# mapleCUx_med_011.net
KiCad netlist of a schematic drawn in EAGLE
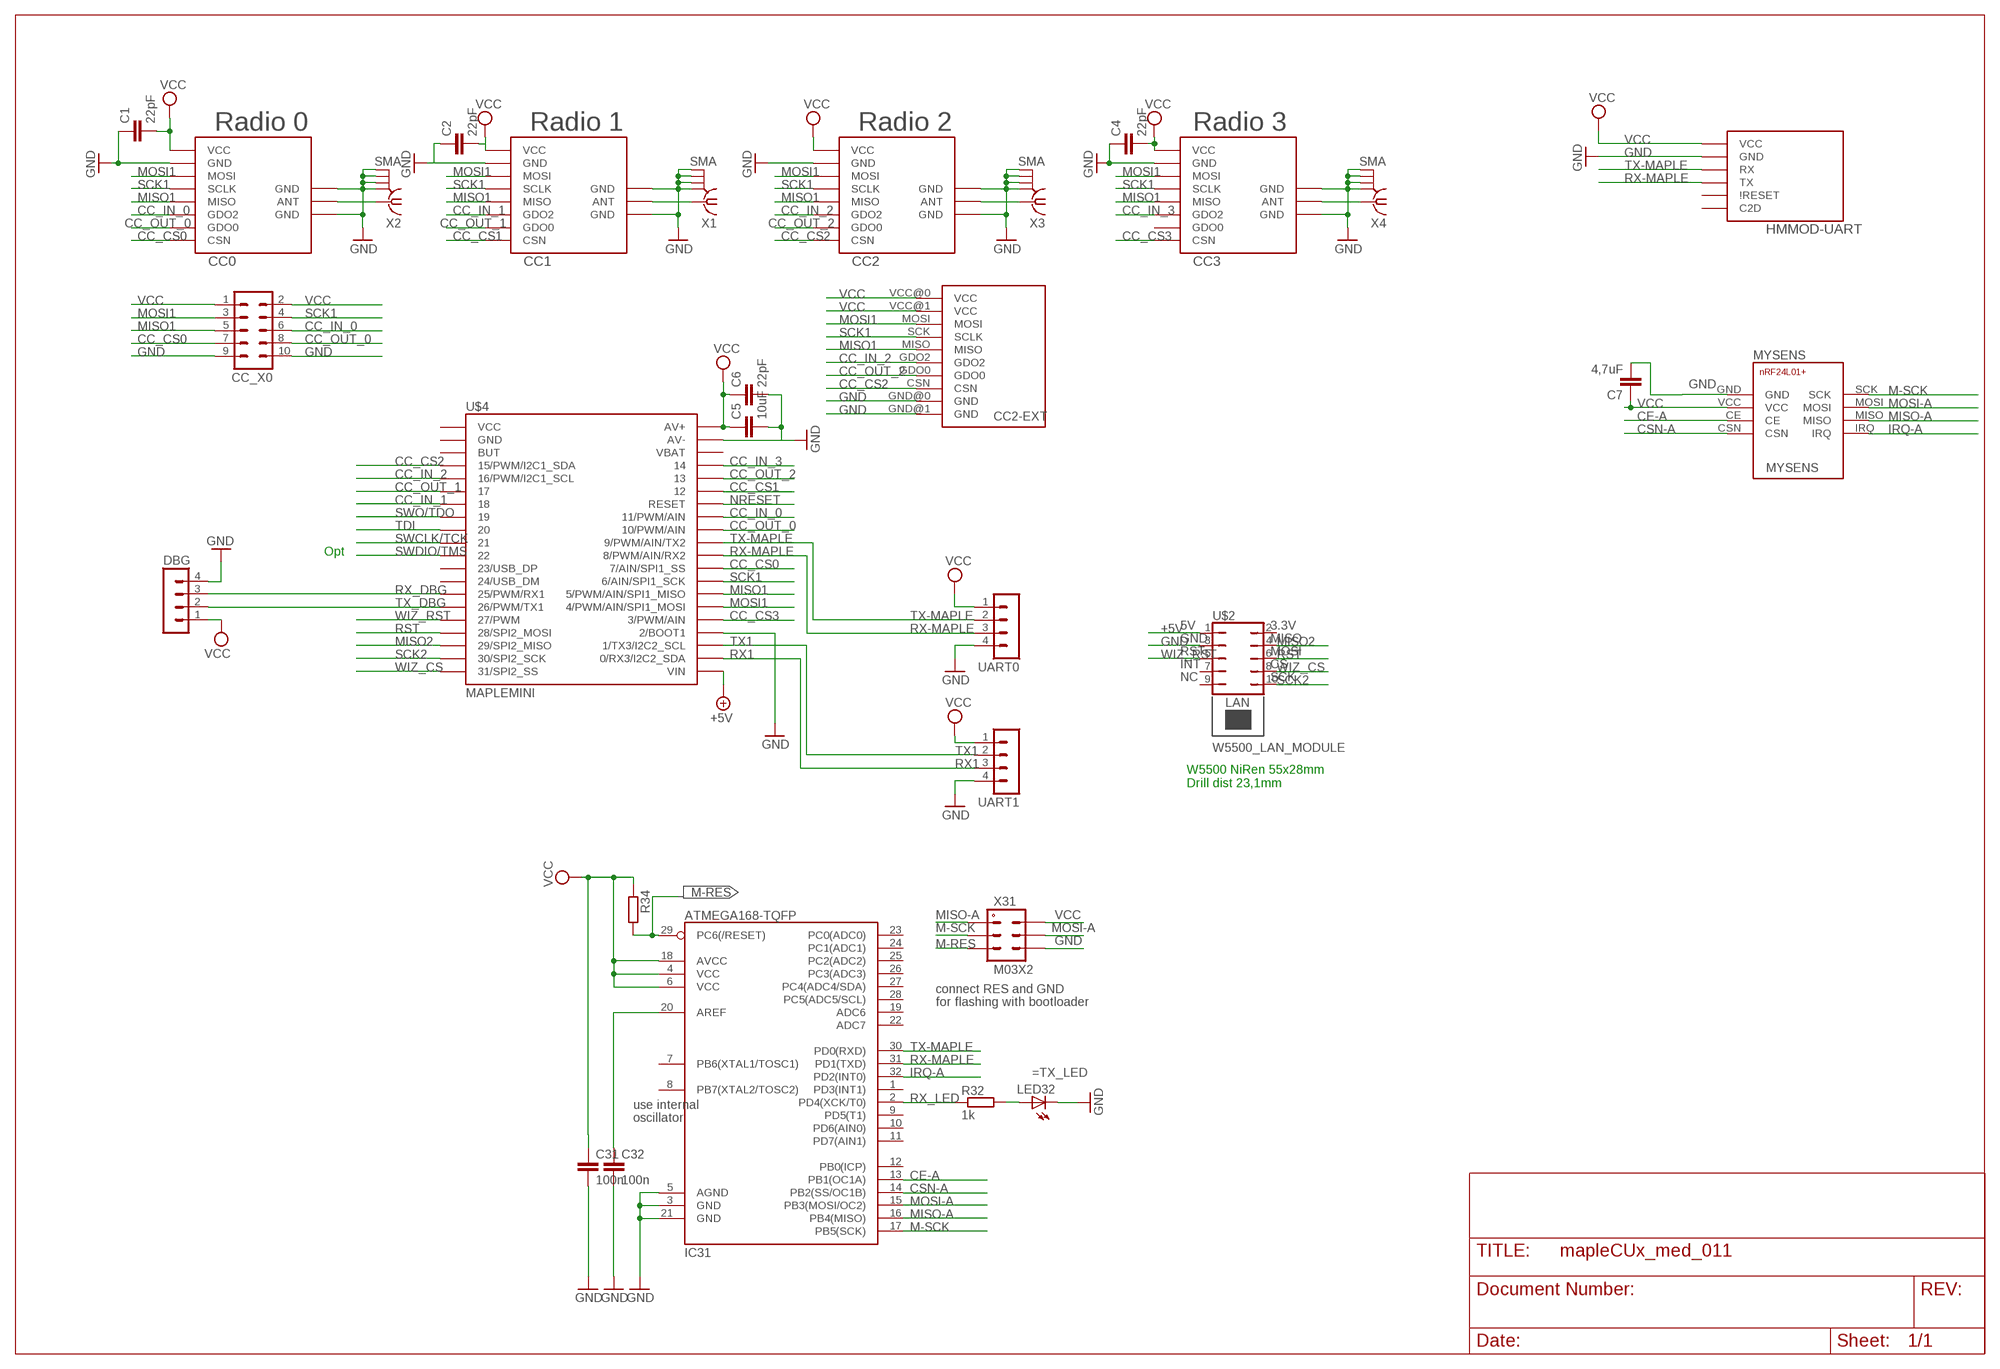
[diagram p0: schematic, sheet 1]

(export (version "E")
  (design (tool "Eeschema 10.0.6"))
  (components
    (comp (ref "C1")
      (value "22pF")
      (footprint "eagle-import:C0805")
      (libsource (lib "eagle-import") (part "C-EUC0805"))
    )
    (comp (ref "C2")
      (value "22pF")
      (footprint "eagle-import:C0805")
      (libsource (lib "eagle-import") (part "C-EUC0805"))
    )
    (comp (ref "C4")
      (value "22pF")
      (footprint "eagle-import:C0805")
      (libsource (lib "eagle-import") (part "C-EUC0805"))
    )
    (comp (ref "C5")
      (value "10uF")
      (footprint "eagle-import:C1210")
      (libsource (lib "eagle-import") (part "C-EUC1210"))
    )
    (comp (ref "C6")
      (value "22pF")
      (footprint "eagle-import:C0805")
      (libsource (lib "eagle-import") (part "C-EUC0805"))
    )
    (comp (ref "C7")
      (value "4,7uF")
      (footprint "eagle-import:C1210")
      (libsource (lib "eagle-import") (part "C-EUC1210"))
    )
    (comp (ref "C31")
      (value "100n")
      (footprint "eagle-import:C0805")
      (libsource (lib "eagle-import") (part "C-EUC0805"))
    )
    (comp (ref "C32")
      (value "100n")
      (footprint "eagle-import:C0805")
      (libsource (lib "eagle-import") (part "C-EUC0805"))
    )
    (comp (ref "CC0")
      (value "CC1101_MODULE1SMD")
      (footprint "eagle-import:CC1101_MODULE1_SMD")
      (libsource (lib "eagle-import") (part "CC1101_MODULE1SMD"))
    )
    (comp (ref "CC1")
      (value "CC1101_MODULE1SMD")
      (footprint "eagle-import:CC1101_MODULE1_SMD")
      (libsource (lib "eagle-import") (part "CC1101_MODULE1SMD"))
    )
    (comp (ref "CC2")
      (value "CC1101_MODULE1SMD")
      (footprint "eagle-import:CC1101_MODULE1_SMD")
      (libsource (lib "eagle-import") (part "CC1101_MODULE1SMD"))
    )
    (comp (ref "CC2-EXT")
      (value "CC1101_MODULE3_DIL")
      (footprint "eagle-import:CC1101_MODULE3_DIL")
      (libsource (lib "eagle-import") (part "CC1101_MODULE3_DIL"))
    )
    (comp (ref "CC3")
      (value "CC1101_MODULE1SMD")
      (footprint "eagle-import:CC1101_MODULE1_SMD")
      (libsource (lib "eagle-import") (part "CC1101_MODULE1SMD"))
    )
    (comp (ref "CC_X0")
      (value "MA05-2")
      (footprint "eagle-import:MA05-2")
      (libsource (lib "eagle-import") (part "MA05-2"))
    )
    (comp (ref "DBG")
      (value "MA04-1")
      (footprint "eagle-import:MA04-1")
      (libsource (lib "eagle-import") (part "MA04-1"))
    )
    (comp (ref "HMMOD-UART")
      (value "HM-MOD-UARTDIL")
      (footprint "eagle-import:HM-MOD-UART-DIL")
      (libsource (lib "eagle-import") (part "HM-MOD-UARTDIL"))
    )
    (comp (ref "IC31")
      (value "ATMEGA168-TQFP")
      (footprint "eagle-import:TQFP32-08")
      (libsource (lib "eagle-import") (part "ATMEGA168-TQFP"))
    )
    (comp (ref "LED32")
      (value "LEDCHIPLED_0805")
      (footprint "eagle-import:CHIPLED_0805")
      (libsource (lib "eagle-import") (part "LEDCHIPLED_0805"))
    )
    (comp (ref "MYSENS")
      (value "NRF24L01+SMD")
      (footprint "eagle-import:NRF24L01+SMD")
      (libsource (lib "eagle-import") (part "NRF24L01+SMD"))
    )
    (comp (ref "R32")
      (value "1k")
      (footprint "eagle-import:R0805")
      (libsource (lib "eagle-import") (part "R-EU_R0805"))
    )
    (comp (ref "R34")
      (value "R-EU_R0805")
      (footprint "eagle-import:R0805")
      (libsource (lib "eagle-import") (part "R-EU_R0805"))
    )
    (comp (ref "U$2")
      (value "W5500_LAN_MODULE")
      (footprint "eagle-import:W5500_LAN_MODULE-1")
      (libsource (lib "eagle-import") (part "W5500_LAN_MODULE"))
    )
    (comp (ref "U$4")
      (value "MAPLEMINI")
      (footprint "eagle-import:20-DIP")
      (libsource (lib "eagle-import") (part "MAPLEMINI"))
    )
    (comp (ref "UART0")
      (value "MA04-1")
      (footprint "eagle-import:MA04-1")
      (libsource (lib "eagle-import") (part "MA04-1"))
    )
    (comp (ref "UART1")
      (value "MA04-1")
      (footprint "eagle-import:MA04-1")
      (libsource (lib "eagle-import") (part "MA04-1"))
    )
    (comp (ref "X1")
      (value "SMA")
      (footprint "eagle-import:SMA")
      (libsource (lib "eagle-import") (part "SMA"))
    )
    (comp (ref "X2")
      (value "SMA")
      (footprint "eagle-import:SMA")
      (libsource (lib "eagle-import") (part "SMA"))
    )
    (comp (ref "X3")
      (value "SMA")
      (footprint "eagle-import:SMA")
      (libsource (lib "eagle-import") (part "SMA"))
    )
    (comp (ref "X4")
      (value "SMA")
      (footprint "eagle-import:SMA")
      (libsource (lib "eagle-import") (part "SMA"))
    )
    (comp (ref "X31")
      (value "M03X2")
      (footprint "eagle-import:2X03-1.27MM_SMD")
      (libsource (lib "eagle-import") (part "M03X2"))
    )
  )
  (nets
    (net (code "1") (name "+5V") (class "Default")
      (node (ref "U$2") (pin "1") (pinfunction "1_1") (pintype "passive"))
      (node (ref "U$4") (pin "21") (pinfunction "VIN_21") (pintype "bidirectional"))
    )
    (net (code "2") (name "/CC_CS0") (class "Default")
      (node (ref "CC0") (pin "CSN") (pinfunction "CSN_CSN") (pintype "bidirectional"))
      (node (ref "CC_X0") (pin "7") (pinfunction "7_7") (pintype "passive"))
      (node (ref "U$4") (pin "29") (pinfunction "7/AIN/SPI1_SS_29") (pintype "bidirectional"))
    )
    (net (code "3") (name "/CC_CS1") (class "Default")
      (node (ref "CC1") (pin "CSN") (pinfunction "CSN_CSN") (pintype "bidirectional"))
      (node (ref "U$4") (pin "35") (pinfunction "12_35") (pintype "bidirectional"))
    )
    (net (code "4") (name "/CC_CS2") (class "Default")
      (node (ref "CC2") (pin "CSN") (pinfunction "CSN_CSN") (pintype "bidirectional"))
      (node (ref "CC2-EXT") (pin "CSN") (pinfunction "CSN_CSN") (pintype "bidirectional"))
      (node (ref "U$4") (pin "4") (pinfunction "15/PWM/I2C1_SDA_4") (pintype "bidirectional"))
    )
    (net (code "5") (name "/CC_CS3") (class "Default")
      (node (ref "CC3") (pin "CSN") (pinfunction "CSN_CSN") (pintype "bidirectional"))
      (node (ref "U$4") (pin "25") (pinfunction "3/PWM/AIN_25") (pintype "bidirectional"))
    )
    (net (code "6") (name "/CC_IN_0") (class "Default")
      (node (ref "CC0") (pin "GDO2") (pinfunction "GDO2_GDO2") (pintype "bidirectional"))
      (node (ref "CC_X0") (pin "6") (pinfunction "6_6") (pintype "passive"))
      (node (ref "U$4") (pin "33") (pinfunction "11/PWM/AIN_33") (pintype "bidirectional"))
    )
    (net (code "7") (name "/CC_IN_1") (class "Default")
      (node (ref "CC1") (pin "GDO2") (pinfunction "GDO2_GDO2") (pintype "bidirectional"))
      (node (ref "U$4") (pin "7") (pinfunction "18_7") (pintype "bidirectional"))
    )
    (net (code "8") (name "/CC_IN_2") (class "Default")
      (node (ref "CC2") (pin "GDO2") (pinfunction "GDO2_GDO2") (pintype "bidirectional"))
      (node (ref "CC2-EXT") (pin "GDO2") (pinfunction "GDO2_GDO2") (pintype "bidirectional"))
      (node (ref "U$4") (pin "5") (pinfunction "16/PWM/I2C1_SCL_5") (pintype "bidirectional"))
    )
    (net (code "9") (name "/CC_IN_3") (class "Default")
      (node (ref "CC3") (pin "GDO2") (pinfunction "GDO2_GDO2") (pintype "bidirectional"))
      (node (ref "U$4") (pin "37") (pinfunction "14_37") (pintype "bidirectional"))
    )
    (net (code "10") (name "/CC_OUT_0") (class "Default")
      (node (ref "CC0") (pin "GDO0") (pinfunction "GDO0_GDO0") (pintype "bidirectional"))
      (node (ref "CC_X0") (pin "8") (pinfunction "8_8") (pintype "passive"))
      (node (ref "U$4") (pin "32") (pinfunction "10/PWM/AIN_32") (pintype "bidirectional"))
    )
    (net (code "11") (name "/CC_OUT_1") (class "Default")
      (node (ref "CC1") (pin "GDO0") (pinfunction "GDO0_GDO0") (pintype "bidirectional"))
      (node (ref "U$4") (pin "6") (pinfunction "17_6") (pintype "bidirectional"))
    )
    (net (code "12") (name "/CC_OUT_2") (class "Default")
      (node (ref "CC2") (pin "GDO0") (pinfunction "GDO0_GDO0") (pintype "bidirectional"))
      (node (ref "CC2-EXT") (pin "GDO0") (pinfunction "GDO0_GDO0") (pintype "bidirectional"))
      (node (ref "U$4") (pin "36") (pinfunction "13_36") (pintype "bidirectional"))
    )
    (net (code "13") (name "/CE-A") (class "Default")
      (node (ref "IC31") (pin "13") (pinfunction "PB1(OC1A)_13") (pintype "bidirectional"))
      (node (ref "MYSENS") (pin "CE") (pinfunction "CE_CE") (pintype "bidirectional"))
    )
    (net (code "14") (name "/CSN-A") (class "Default")
      (node (ref "IC31") (pin "14") (pinfunction "PB2(SS/OC1B)_14") (pintype "bidirectional"))
      (node (ref "MYSENS") (pin "CSN") (pinfunction "CSN_CSN") (pintype "bidirectional"))
    )
    (net (code "15") (name "/IRQ-A") (class "Default")
      (node (ref "IC31") (pin "32") (pinfunction "PD2(INT0)_32") (pintype "bidirectional"))
      (node (ref "MYSENS") (pin "IRQ") (pinfunction "IRQ_IRQ") (pintype "bidirectional"))
    )
    (net (code "16") (name "/M-RES") (class "Default")
      (node (ref "IC31") (pin "29") (pinfunction "PC6(/RESET)_29") (pintype "bidirectional"))
      (node (ref "R34") (pin "2") (pinfunction "2_2") (pintype "passive"))
      (node (ref "X31") (pin "P$5") (pinfunction "5_P$5") (pintype "passive"))
    )
    (net (code "17") (name "/M-SCK") (class "Default")
      (node (ref "IC31") (pin "17") (pinfunction "PB5(SCK)_17") (pintype "bidirectional"))
      (node (ref "MYSENS") (pin "SCK") (pinfunction "SCK_SCK") (pintype "bidirectional"))
      (node (ref "X31") (pin "P$3") (pinfunction "3_P$3") (pintype "passive"))
    )
    (net (code "18") (name "/MISO-A") (class "Default")
      (node (ref "IC31") (pin "16") (pinfunction "PB4(MISO)_16") (pintype "bidirectional"))
      (node (ref "MYSENS") (pin "MISO") (pinfunction "MISO_MISO") (pintype "bidirectional"))
      (node (ref "X31") (pin "P$1") (pinfunction "1_P$1") (pintype "passive"))
    )
    (net (code "19") (name "/MISO1") (class "Default")
      (node (ref "CC0") (pin "MISO") (pinfunction "MISO_MISO") (pintype "bidirectional"))
      (node (ref "CC1") (pin "MISO") (pinfunction "MISO_MISO") (pintype "bidirectional"))
      (node (ref "CC2") (pin "MISO") (pinfunction "MISO_MISO") (pintype "bidirectional"))
      (node (ref "CC2-EXT") (pin "MISO") (pinfunction "MISO_MISO") (pintype "bidirectional"))
      (node (ref "CC3") (pin "MISO") (pinfunction "MISO_MISO") (pintype "bidirectional"))
      (node (ref "CC_X0") (pin "5") (pinfunction "5_5") (pintype "passive"))
      (node (ref "U$4") (pin "27") (pinfunction "5/PWM/AIN/SPI1_MISO_27") (pintype "bidirectional"))
    )
    (net (code "20") (name "/MISO2") (class "Default")
      (node (ref "U$2") (pin "4") (pinfunction "4_4") (pintype "passive"))
      (node (ref "U$4") (pin "18") (pinfunction "29/SPI2_MISO_18") (pintype "bidirectional"))
    )
    (net (code "21") (name "/MOSI-A") (class "Default")
      (node (ref "IC31") (pin "15") (pinfunction "PB3(MOSI/OC2)_15") (pintype "bidirectional"))
      (node (ref "MYSENS") (pin "MOSI") (pinfunction "MOSI_MOSI") (pintype "bidirectional"))
      (node (ref "X31") (pin "P$4") (pinfunction "4_P$4") (pintype "passive"))
    )
    (net (code "22") (name "/MOSI1") (class "Default")
      (node (ref "CC0") (pin "MOSI") (pinfunction "MOSI_MOSI") (pintype "bidirectional"))
      (node (ref "CC1") (pin "MOSI") (pinfunction "MOSI_MOSI") (pintype "bidirectional"))
      (node (ref "CC2") (pin "MOSI") (pinfunction "MOSI_MOSI") (pintype "bidirectional"))
      (node (ref "CC2-EXT") (pin "MOSI") (pinfunction "MOSI_MOSI") (pintype "bidirectional"))
      (node (ref "CC3") (pin "MOSI") (pinfunction "MOSI_MOSI") (pintype "bidirectional"))
      (node (ref "CC_X0") (pin "3") (pinfunction "3_3") (pintype "passive"))
      (node (ref "U$4") (pin "26") (pinfunction "4/PWM/AIN/SPI1_MOSI_26") (pintype "bidirectional"))
    )
    (net (code "23") (name "/NRESET") (class "Default")
      (node (ref "U$4") (pin "34") (pinfunction "RESET_34") (pintype "bidirectional"))
    )
    (net (code "24") (name "/RST") (class "Default")
      (node (ref "U$2") (pin "6") (pinfunction "6_6") (pintype "passive"))
      (node (ref "U$4") (pin "17") (pinfunction "28/SPI2_MOSI_17") (pintype "bidirectional"))
    )
    (net (code "25") (name "/RX-MAPLE") (class "Default")
      (node (ref "HMMOD-UART") (pin "5") (pinfunction "TX_5") (pintype "bidirectional"))
      (node (ref "IC31") (pin "31") (pinfunction "PD1(TXD)_31") (pintype "bidirectional"))
      (node (ref "U$4") (pin "30") (pinfunction "8/PWM/AIN/RX2_30") (pintype "bidirectional"))
      (node (ref "UART0") (pin "3") (pinfunction "3_3") (pintype "passive"))
    )
    (net (code "26") (name "/RX1") (class "Default")
      (node (ref "U$4") (pin "22") (pinfunction "0/RX3/I2C2_SDA_22") (pintype "bidirectional"))
      (node (ref "UART1") (pin "3") (pinfunction "3_3") (pintype "passive"))
    )
    (net (code "27") (name "/RX_DBG") (class "Default")
      (node (ref "DBG") (pin "3") (pinfunction "3_3") (pintype "passive"))
      (node (ref "U$4") (pin "14") (pinfunction "25/PWM/RX1_14") (pintype "bidirectional"))
    )
    (net (code "28") (name "/RX_LED") (class "Default")
      (node (ref "IC31") (pin "2") (pinfunction "PD4(XCK/T0)_2") (pintype "bidirectional"))
      (node (ref "R32") (pin "1") (pinfunction "1_1") (pintype "passive"))
    )
    (net (code "29") (name "/SCK1") (class "Default")
      (node (ref "CC0") (pin "SCLK") (pinfunction "SCLK_SCLK") (pintype "bidirectional"))
      (node (ref "CC1") (pin "SCLK") (pinfunction "SCLK_SCLK") (pintype "bidirectional"))
      (node (ref "CC2") (pin "SCLK") (pinfunction "SCLK_SCLK") (pintype "bidirectional"))
      (node (ref "CC2-EXT") (pin "SCK") (pinfunction "SCLK_SCK") (pintype "bidirectional"))
      (node (ref "CC3") (pin "SCLK") (pinfunction "SCLK_SCLK") (pintype "bidirectional"))
      (node (ref "CC_X0") (pin "4") (pinfunction "4_4") (pintype "passive"))
      (node (ref "U$4") (pin "28") (pinfunction "6/AIN/SPI1_SCK_28") (pintype "bidirectional"))
    )
    (net (code "30") (name "/SCK2") (class "Default")
      (node (ref "U$2") (pin "10") (pinfunction "10_10") (pintype "passive"))
      (node (ref "U$4") (pin "19") (pinfunction "30/SPI2_SCK_19") (pintype "bidirectional"))
    )
    (net (code "31") (name "/SWCLK{slash}TCK") (class "Default")
      (node (ref "U$4") (pin "10") (pinfunction "21_10") (pintype "bidirectional"))
    )
    (net (code "32") (name "/SWDIO{slash}TMS") (class "Default")
      (node (ref "U$4") (pin "11") (pinfunction "22_11") (pintype "bidirectional"))
    )
    (net (code "33") (name "/SWO{slash}TDO") (class "Default")
      (node (ref "U$4") (pin "8") (pinfunction "19_8") (pintype "bidirectional"))
    )
    (net (code "34") (name "/TDI") (class "Default")
      (node (ref "U$4") (pin "9") (pinfunction "20_9") (pintype "bidirectional"))
    )
    (net (code "35") (name "/TX-MAPLE") (class "Default")
      (node (ref "HMMOD-UART") (pin "6") (pinfunction "RX_6") (pintype "bidirectional"))
      (node (ref "IC31") (pin "30") (pinfunction "PD0(RXD)_30") (pintype "bidirectional"))
      (node (ref "U$4") (pin "31") (pinfunction "9/PWM/AIN/TX2_31") (pintype "bidirectional"))
      (node (ref "UART0") (pin "2") (pinfunction "2_2") (pintype "passive"))
    )
    (net (code "36") (name "/TX1") (class "Default")
      (node (ref "U$4") (pin "23") (pinfunction "1/TX3/I2C2_SCL_23") (pintype "bidirectional"))
      (node (ref "UART1") (pin "2") (pinfunction "2_2") (pintype "passive"))
    )
    (net (code "37") (name "/TX_DBG") (class "Default")
      (node (ref "DBG") (pin "2") (pinfunction "2_2") (pintype "passive"))
      (node (ref "U$4") (pin "15") (pinfunction "26/PWM/TX1_15") (pintype "bidirectional"))
    )
    (net (code "38") (name "/WIZ_CS") (class "Default")
      (node (ref "U$2") (pin "8") (pinfunction "8_8") (pintype "passive"))
      (node (ref "U$4") (pin "20") (pinfunction "31/SPI2_SS_20") (pintype "bidirectional"))
    )
    (net (code "39") (name "/WIZ_RST") (class "Default")
      (node (ref "U$2") (pin "5") (pinfunction "5_5") (pintype "passive"))
      (node (ref "U$4") (pin "16") (pinfunction "27/PWM_16") (pintype "bidirectional"))
    )
    (net (code "40") (name "GND") (class "Default")
      (node (ref "C1") (pin "1") (pinfunction "1_1") (pintype "passive"))
      (node (ref "C2") (pin "1") (pinfunction "1_1") (pintype "passive"))
      (node (ref "C31") (pin "2") (pinfunction "2_2") (pintype "passive"))
      (node (ref "C32") (pin "2") (pinfunction "2_2") (pintype "passive"))
      (node (ref "C4") (pin "1") (pinfunction "1_1") (pintype "passive"))
      (node (ref "C5") (pin "2") (pinfunction "2_2") (pintype "passive"))
      (node (ref "C6") (pin "2") (pinfunction "2_2") (pintype "passive"))
      (node (ref "C7") (pin "2") (pinfunction "2_2") (pintype "passive"))
      (node (ref "CC0") (pin "GND@0") (pinfunction "GND_GND@0") (pintype "power_in"))
      (node (ref "CC0") (pin "GND@1") (pinfunction "GND_GND@1") (pintype "power_in"))
      (node (ref "CC0") (pin "GND@2") (pinfunction "GND_GND@2") (pintype "power_in"))
      (node (ref "CC1") (pin "GND@0") (pinfunction "GND_GND@0") (pintype "power_in"))
      (node (ref "CC1") (pin "GND@1") (pinfunction "GND_GND@1") (pintype "power_in"))
      (node (ref "CC1") (pin "GND@2") (pinfunction "GND_GND@2") (pintype "power_in"))
      (node (ref "CC2") (pin "GND@0") (pinfunction "GND_GND@0") (pintype "power_in"))
      (node (ref "CC2") (pin "GND@1") (pinfunction "GND_GND@1") (pintype "power_in"))
      (node (ref "CC2") (pin "GND@2") (pinfunction "GND_GND@2") (pintype "power_in"))
      (node (ref "CC2-EXT") (pin "GND@0") (pinfunction "GND_GND@0") (pintype "power_in"))
      (node (ref "CC2-EXT") (pin "GND@1") (pinfunction "GND_GND@1") (pintype "power_in"))
      (node (ref "CC3") (pin "GND@0") (pinfunction "GND_GND@0") (pintype "power_in"))
      (node (ref "CC3") (pin "GND@1") (pinfunction "GND_GND@1") (pintype "power_in"))
      (node (ref "CC3") (pin "GND@2") (pinfunction "GND_GND@2") (pintype "power_in"))
      (node (ref "CC_X0") (pin "10") (pinfunction "10_10") (pintype "passive"))
      (node (ref "CC_X0") (pin "9") (pinfunction "9_9") (pintype "passive"))
      (node (ref "DBG") (pin "4") (pinfunction "4_4") (pintype "passive"))
      (node (ref "HMMOD-UART") (pin "2") (pinfunction "GND_2") (pintype "power_in"))
      (node (ref "IC31") (pin "21") (pinfunction "GND_21") (pintype "bidirectional"))
      (node (ref "IC31") (pin "3") (pinfunction "GND_3") (pintype "bidirectional"))
      (node (ref "IC31") (pin "5") (pinfunction "AGND_5") (pintype "bidirectional"))
      (node (ref "LED32") (pin "C") (pinfunction "C_C") (pintype "passive"))
      (node (ref "MYSENS") (pin "GND") (pinfunction "GND_GND") (pintype "power_in"))
      (node (ref "U$2") (pin "3") (pinfunction "3_3") (pintype "passive"))
      (node (ref "U$4") (pin "24") (pinfunction "2/BOOT1_24") (pintype "bidirectional"))
      (node (ref "U$4") (pin "39") (pinfunction "AV-_39") (pintype "bidirectional"))
      (node (ref "UART0") (pin "4") (pinfunction "4_4") (pintype "passive"))
      (node (ref "UART1") (pin "4") (pinfunction "4_4") (pintype "passive"))
      (node (ref "X1") (pin "GND@1") (pinfunction "2_GND@1") (pintype "passive"))
      (node (ref "X1") (pin "GND@2") (pinfunction "3_GND@2") (pintype "passive"))
      (node (ref "X1") (pin "GND@3") (pinfunction "4_GND@3") (pintype "passive"))
      (node (ref "X1") (pin "GND@4") (pinfunction "5_GND@4") (pintype "passive"))
      (node (ref "X2") (pin "GND@1") (pinfunction "2_GND@1") (pintype "passive"))
      (node (ref "X2") (pin "GND@2") (pinfunction "3_GND@2") (pintype "passive"))
      (node (ref "X2") (pin "GND@3") (pinfunction "4_GND@3") (pintype "passive"))
      (node (ref "X2") (pin "GND@4") (pinfunction "5_GND@4") (pintype "passive"))
      (node (ref "X3") (pin "GND@1") (pinfunction "2_GND@1") (pintype "passive"))
      (node (ref "X3") (pin "GND@2") (pinfunction "3_GND@2") (pintype "passive"))
      (node (ref "X3") (pin "GND@3") (pinfunction "4_GND@3") (pintype "passive"))
      (node (ref "X3") (pin "GND@4") (pinfunction "5_GND@4") (pintype "passive"))
      (node (ref "X31") (pin "P$6") (pinfunction "6_P$6") (pintype "passive"))
      (node (ref "X4") (pin "GND@1") (pinfunction "2_GND@1") (pintype "passive"))
      (node (ref "X4") (pin "GND@2") (pinfunction "3_GND@2") (pintype "passive"))
      (node (ref "X4") (pin "GND@3") (pinfunction "4_GND@3") (pintype "passive"))
      (node (ref "X4") (pin "GND@4") (pinfunction "5_GND@4") (pintype "passive"))
    )
    (net (code "41") (name "Net-(CC0-PadANT)") (class "Default")
      (node (ref "CC0") (pin "ANT") (pinfunction "ANT_ANT") (pintype "output"))
      (node (ref "X2") (pin "1") (pinfunction "1_1") (pintype "passive"))
    )
    (net (code "42") (name "Net-(CC1-PadANT)") (class "Default")
      (node (ref "CC1") (pin "ANT") (pinfunction "ANT_ANT") (pintype "output"))
      (node (ref "X1") (pin "1") (pinfunction "1_1") (pintype "passive"))
    )
    (net (code "43") (name "Net-(CC2-PadANT)") (class "Default")
      (node (ref "CC2") (pin "ANT") (pinfunction "ANT_ANT") (pintype "output"))
      (node (ref "X3") (pin "1") (pinfunction "1_1") (pintype "passive"))
    )
    (net (code "44") (name "Net-(CC3-PadANT)") (class "Default")
      (node (ref "CC3") (pin "ANT") (pinfunction "ANT_ANT") (pintype "output"))
      (node (ref "X4") (pin "1") (pinfunction "1_1") (pintype "passive"))
    )
    (net (code "45") (name "Net-(IC31-AREF)") (class "Default")
      (node (ref "C32") (pin "1") (pinfunction "1_1") (pintype "passive"))
      (node (ref "IC31") (pin "20") (pinfunction "AREF_20") (pintype "bidirectional"))
    )
    (net (code "46") (name "Net-(LED32-PadA)") (class "Default")
      (node (ref "LED32") (pin "A") (pinfunction "A_A") (pintype "passive"))
      (node (ref "R32") (pin "2") (pinfunction "2_2") (pintype "passive"))
    )
    (net (code "47") (name "VCC") (class "Default")
      (node (ref "C1") (pin "2") (pinfunction "2_2") (pintype "passive"))
      (node (ref "C2") (pin "2") (pinfunction "2_2") (pintype "passive"))
      (node (ref "C31") (pin "1") (pinfunction "1_1") (pintype "passive"))
      (node (ref "C4") (pin "2") (pinfunction "2_2") (pintype "passive"))
      (node (ref "C5") (pin "1") (pinfunction "1_1") (pintype "passive"))
      (node (ref "C6") (pin "1") (pinfunction "1_1") (pintype "passive"))
      (node (ref "C7") (pin "1") (pinfunction "1_1") (pintype "passive"))
      (node (ref "CC0") (pin "VCC") (pinfunction "VCC_VCC") (pintype "power_in"))
      (node (ref "CC1") (pin "VCC") (pinfunction "VCC_VCC") (pintype "power_in"))
      (node (ref "CC2") (pin "VCC") (pinfunction "VCC_VCC") (pintype "power_in"))
      (node (ref "CC2-EXT") (pin "VCC@0") (pinfunction "VCC_VCC@0") (pintype "power_in"))
      (node (ref "CC2-EXT") (pin "VCC@1") (pinfunction "VCC_VCC@1") (pintype "power_in"))
      (node (ref "CC3") (pin "VCC") (pinfunction "VCC_VCC") (pintype "power_in"))
      (node (ref "CC_X0") (pin "1") (pinfunction "1_1") (pintype "passive"))
      (node (ref "CC_X0") (pin "2") (pinfunction "2_2") (pintype "passive"))
      (node (ref "DBG") (pin "1") (pinfunction "1_1") (pintype "passive"))
      (node (ref "HMMOD-UART") (pin "1") (pinfunction "VCC_1") (pintype "power_in"))
      (node (ref "IC31") (pin "18") (pinfunction "AVCC_18") (pintype "bidirectional"))
      (node (ref "IC31") (pin "4") (pinfunction "VCC_4") (pintype "bidirectional"))
      (node (ref "IC31") (pin "6") (pinfunction "VCC_6") (pintype "bidirectional"))
      (node (ref "MYSENS") (pin "VCC") (pinfunction "VCC_VCC") (pintype "power_in"))
      (node (ref "R34") (pin "1") (pinfunction "1_1") (pintype "passive"))
      (node (ref "U$4") (pin "40") (pinfunction "AV+_40") (pintype "bidirectional"))
      (node (ref "UART0") (pin "1") (pinfunction "1_1") (pintype "passive"))
      (node (ref "UART1") (pin "1") (pinfunction "1_1") (pintype "passive"))
      (node (ref "X31") (pin "P$2") (pinfunction "2_P$2") (pintype "passive"))
    )
    (net (code "48") (name "unconnected-(CC3-PadGDO0)") (class "Default")
      (node (ref "CC3") (pin "GDO0") (pinfunction "GDO0_GDO0") (pintype "bidirectional"))
    )
    (net (code "49") (name "unconnected-(HMMOD-UART-C2D-Pad3)") (class "Default")
      (node (ref "HMMOD-UART") (pin "3") (pinfunction "C2D_3") (pintype "bidirectional"))
    )
    (net (code "50") (name "unconnected-(HMMOD-UART-\\~{RESET}-Pad4)") (class "Default")
      (node (ref "HMMOD-UART") (pin "4") (pinfunction "\\~{RESET}_4") (pintype "bidirectional"))
    )
    (net (code "51") (name "unconnected-(IC31-ADC6-Pad19)") (class "Default")
      (node (ref "IC31") (pin "19") (pinfunction "ADC6_19") (pintype "bidirectional"))
    )
    (net (code "52") (name "unconnected-(IC31-ADC7-Pad22)") (class "Default")
      (node (ref "IC31") (pin "22") (pinfunction "ADC7_22") (pintype "bidirectional"))
    )
    (net (code "53") (name "unconnected-(IC31-PB0(ICP)-Pad12)") (class "Default")
      (node (ref "IC31") (pin "12") (pinfunction "PB0(ICP)_12") (pintype "bidirectional"))
    )
    (net (code "54") (name "unconnected-(IC31-PB6(XTAL1{slash}TOSC1)-Pad7)") (class "Default")
      (node (ref "IC31") (pin "7") (pinfunction "PB6(XTAL1/TOSC1)_7") (pintype "bidirectional"))
    )
    (net (code "55") (name "unconnected-(IC31-PB7(XTAL2{slash}TOSC2)-Pad8)") (class "Default")
      (node (ref "IC31") (pin "8") (pinfunction "PB7(XTAL2/TOSC2)_8") (pintype "bidirectional"))
    )
    (net (code "56") (name "unconnected-(IC31-PC0(ADC0)-Pad23)") (class "Default")
      (node (ref "IC31") (pin "23") (pinfunction "PC0(ADC0)_23") (pintype "bidirectional"))
    )
    (net (code "57") (name "unconnected-(IC31-PC1(ADC1)-Pad24)") (class "Default")
      (node (ref "IC31") (pin "24") (pinfunction "PC1(ADC1)_24") (pintype "bidirectional"))
    )
    (net (code "58") (name "unconnected-(IC31-PC2(ADC2)-Pad25)") (class "Default")
      (node (ref "IC31") (pin "25") (pinfunction "PC2(ADC2)_25") (pintype "bidirectional"))
    )
    (net (code "59") (name "unconnected-(IC31-PC3(ADC3)-Pad26)") (class "Default")
      (node (ref "IC31") (pin "26") (pinfunction "PC3(ADC3)_26") (pintype "bidirectional"))
    )
    (net (code "60") (name "unconnected-(IC31-PC4(ADC4{slash}SDA)-Pad27)") (class "Default")
      (node (ref "IC31") (pin "27") (pinfunction "PC4(ADC4/SDA)_27") (pintype "bidirectional"))
    )
    (net (code "61") (name "unconnected-(IC31-PC5(ADC5{slash}SCL)-Pad28)") (class "Default")
      (node (ref "IC31") (pin "28") (pinfunction "PC5(ADC5/SCL)_28") (pintype "bidirectional"))
    )
    (net (code "62") (name "unconnected-(IC31-PD3(INT1)-Pad1)") (class "Default")
      (node (ref "IC31") (pin "1") (pinfunction "PD3(INT1)_1") (pintype "bidirectional"))
    )
    (net (code "63") (name "unconnected-(IC31-PD5(T1)-Pad9)") (class "Default")
      (node (ref "IC31") (pin "9") (pinfunction "PD5(T1)_9") (pintype "bidirectional"))
    )
    (net (code "64") (name "unconnected-(IC31-PD6(AIN0)-Pad10)") (class "Default")
      (node (ref "IC31") (pin "10") (pinfunction "PD6(AIN0)_10") (pintype "bidirectional"))
    )
    (net (code "65") (name "unconnected-(IC31-PD7(AIN1)-Pad11)") (class "Default")
      (node (ref "IC31") (pin "11") (pinfunction "PD7(AIN1)_11") (pintype "bidirectional"))
    )
    (net (code "66") (name "unconnected-(U$2-Pad2)") (class "Default")
      (node (ref "U$2") (pin "2") (pinfunction "2_2") (pintype "passive"))
    )
    (net (code "67") (name "unconnected-(U$2-Pad7)") (class "Default")
      (node (ref "U$2") (pin "7") (pinfunction "7_7") (pintype "passive"))
    )
    (net (code "68") (name "unconnected-(U$2-Pad9)") (class "Default")
      (node (ref "U$2") (pin "9") (pinfunction "9_9") (pintype "passive"))
    )
    (net (code "69") (name "unconnected-(U$4-23{slash}USB_DP-Pad12)") (class "Default")
      (node (ref "U$4") (pin "12") (pinfunction "23/USB_DP_12") (pintype "bidirectional"))
    )
    (net (code "70") (name "unconnected-(U$4-24{slash}USB_DM-Pad13)") (class "Default")
      (node (ref "U$4") (pin "13") (pinfunction "24/USB_DM_13") (pintype "bidirectional"))
    )
    (net (code "71") (name "unconnected-(U$4-BUT-Pad3)") (class "Default")
      (node (ref "U$4") (pin "3") (pinfunction "BUT_3") (pintype "bidirectional"))
    )
    (net (code "72") (name "unconnected-(U$4-GND-Pad2)") (class "Default")
      (node (ref "U$4") (pin "2") (pinfunction "GND_2") (pintype "bidirectional"))
    )
    (net (code "73") (name "unconnected-(U$4-VBAT-Pad38)") (class "Default")
      (node (ref "U$4") (pin "38") (pinfunction "VBAT_38") (pintype "bidirectional"))
    )
    (net (code "74") (name "unconnected-(U$4-VCC-Pad1)") (class "Default")
      (node (ref "U$4") (pin "1") (pinfunction "VCC_1") (pintype "bidirectional"))
    )
  )
)
